# Hex_Link_Rec.net
KiCad netlist of a schematic drawn in Altium Designer
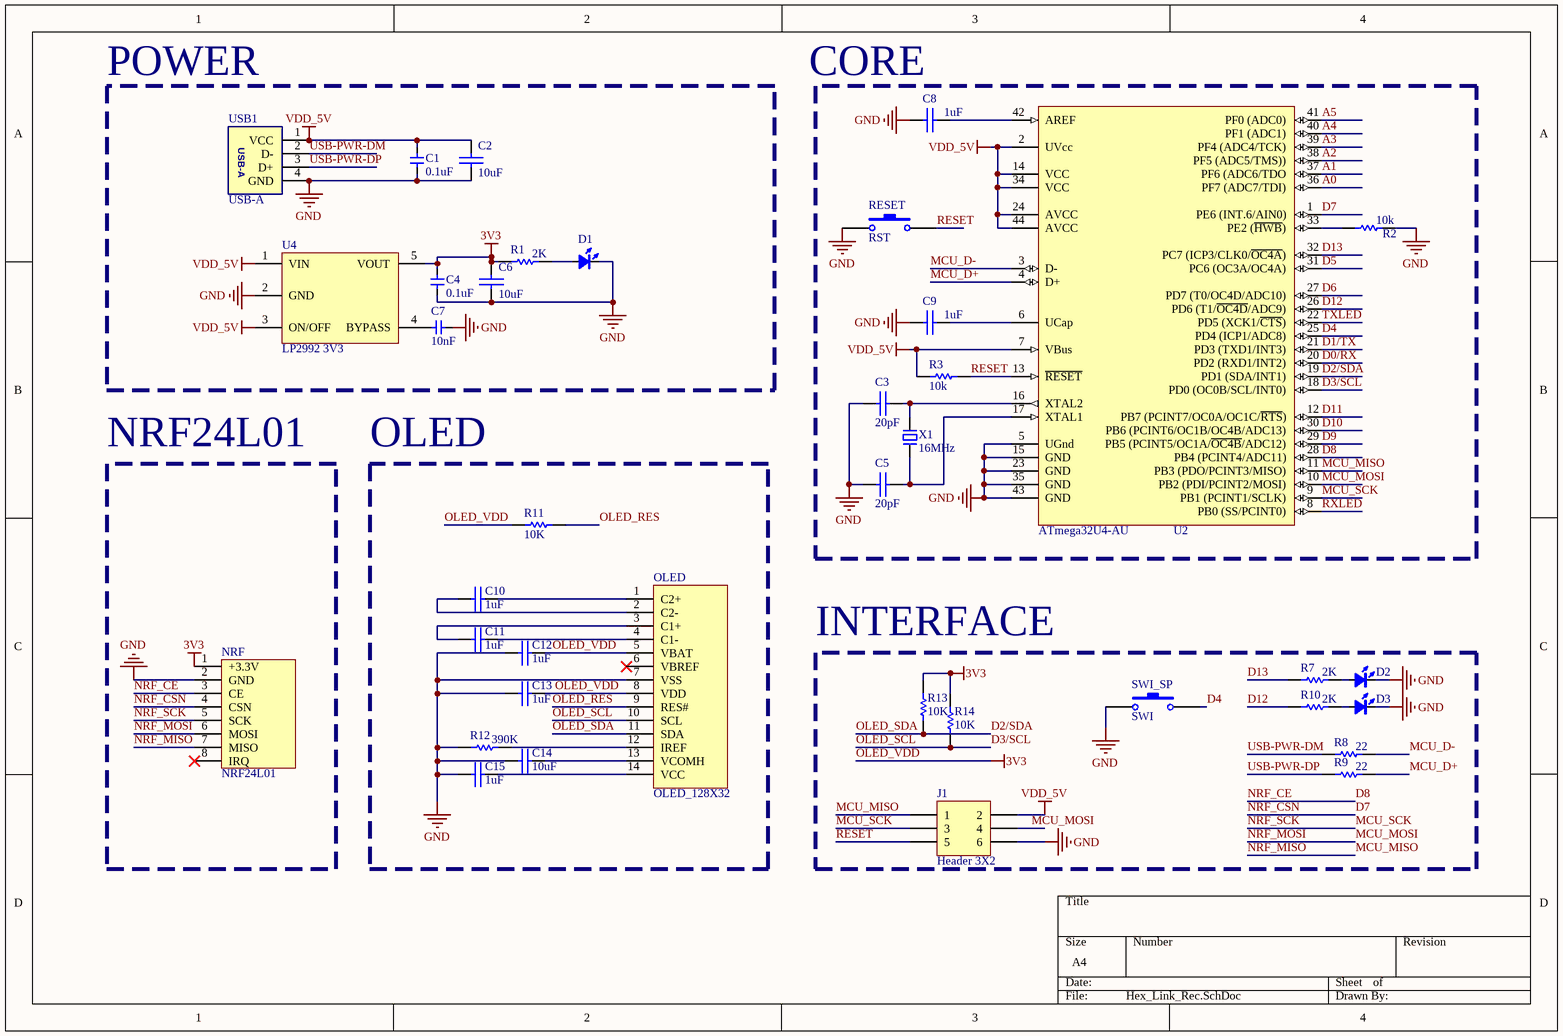
[diagram p0: Hex_Link_Rec.SchDoc]

(export (version "E")
  (design (tool "Eeschema 10.0.6"))
  (components
    (comp (ref "C1")
      (value "0.1uF")
      (footprint "CAP_0402")
      (description "Capacitor")
      (libsource (lib "MyPcbLib") (part "电容-0402"))
    )
    (comp (ref "C2")
      (value "10uF")
      (footprint "CAP_0402")
      (description "无极性电容")
      (libsource (lib "电容") (part "CAP"))
    )
    (comp (ref "C3")
      (value "20pF")
      (footprint "CAP_0402")
      (description "无极性电容")
      (libsource (lib "电容") (part "CAP"))
    )
    (comp (ref "C4")
      (value "0.1uF")
      (footprint "CAP_0402")
      (description "Capacitor")
      (libsource (lib "MyPcbLib") (part "电容-0402"))
    )
    (comp (ref "C5")
      (value "20pF")
      (footprint "CAP_0402")
      (description "无极性电容")
      (libsource (lib "电容") (part "CAP"))
    )
    (comp (ref "C6")
      (value "10uF")
      (footprint "CAP_0402")
      (description "无极性电容")
      (libsource (lib "电容") (part "CAP"))
    )
    (comp (ref "C7")
      (value "10nF")
      (footprint "CAP_0402")
      (description "Capacitor")
      (libsource (lib "MyPcbLib") (part "电容-0402"))
    )
    (comp (ref "C8")
      (value "1uF")
      (footprint "CAP_0402")
      (description "无极性电容")
      (libsource (lib "电容") (part "CAP"))
    )
    (comp (ref "C9")
      (value "1uF")
      (footprint "CAP_0402")
      (description "无极性电容")
      (libsource (lib "电容") (part "CAP"))
    )
    (comp (ref "C10")
      (value "1uF")
      (footprint "CAP_0402")
      (description "无极性电容")
      (libsource (lib "电容") (part "CAP"))
    )
    (comp (ref "C11")
      (value "1uF")
      (footprint "CAP_0402")
      (description "无极性电容")
      (libsource (lib "电容") (part "CAP"))
    )
    (comp (ref "C12")
      (value "1uF")
      (footprint "CAP_0402")
      (description "无极性电容")
      (libsource (lib "电容") (part "CAP"))
    )
    (comp (ref "C13")
      (value "1uF")
      (footprint "CAP_0402")
      (description "无极性电容")
      (libsource (lib "电容") (part "CAP"))
    )
    (comp (ref "C14")
      (value "10uF")
      (footprint "CAP_0402")
      (description "无极性电容")
      (libsource (lib "电容") (part "CAP"))
    )
    (comp (ref "C15")
      (value "1uF")
      (footprint "CAP_0402")
      (description "无极性电容")
      (libsource (lib "电容") (part "CAP"))
    )
    (comp (ref "D1")
      (value "color?")
      (footprint "LED_0402_RED")
      (description "LED")
      (libsource (lib "KitSprout") (part "LED_0402"))
    )
    (comp (ref "D2")
      (value "color?")
      (footprint "LED_0402_RED")
      (description "LED")
      (libsource (lib "KitSprout") (part "LED_0402"))
    )
    (comp (ref "D3")
      (value "color?")
      (footprint "LED_0402_RED")
      (description "LED")
      (libsource (lib "KitSprout") (part "LED_0402"))
    )
    (comp (ref "J1")
      (value "Header 3X2")
      (footprint "HDR2X3")
      (description "Header, 3-Pin, Dual row")
      (fields (field (name "PUBLISHER") "Altium Limited"))
      (libsource (lib "Miscellaneous Connectors") (part "Header 3X2"))
    )
    (comp (ref "NRF")
      (value "NRF24L01")
      (footprint "NRF24l01-SMD")
      (libsource (lib "未分类IC") (part "NRF24L01"))
    )
    (comp (ref "OLED")
      (value "OLED_128X32")
      (footprint "OLED_128X32")
      (libsource (lib "未分类IC") (part "OLED_128X32"))
    )
    (comp (ref "R1") (value "2K") (footprint "RES_0402") (libsource (lib "电阻") (part "RES")))
    (comp (ref "R2") (value "10k") (footprint "RES_0402") (libsource (lib "电阻") (part "RES")))
    (comp (ref "R3") (value "10k") (footprint "RES_0402") (libsource (lib "电阻") (part "RES")))
    (comp (ref "R7") (value "2K") (footprint "RES_0402") (libsource (lib "电阻") (part "RES")))
    (comp (ref "R8") (value "22") (footprint "RES_0402") (libsource (lib "电阻") (part "RES")))
    (comp (ref "R9") (value "22") (footprint "RES_0402") (libsource (lib "电阻") (part "RES")))
    (comp (ref "R10") (value "2K") (footprint "RES_0402") (libsource (lib "电阻") (part "RES")))
    (comp (ref "R11") (value "10K") (footprint "RES_0402") (libsource (lib "电阻") (part "RES")))
    (comp (ref "R12") (value "390K") (footprint "RES_0402") (libsource (lib "电阻") (part "RES")))
    (comp (ref "R13") (value "10K") (footprint "RES_0402") (libsource (lib "电阻") (part "RES")))
    (comp (ref "R14") (value "10K") (footprint "RES_0402") (libsource (lib "电阻") (part "RES")))
    (comp (ref "RESET")
      (value "RST")
      (footprint "SW_PB")
      (description "Switch")
      (fields (field (name "PUBLISHER") "Altium Limited"))
      (libsource (lib "未分类IC") (part "SW-PB"))
    )
    (comp (ref "SWI_SP")
      (value "SWI")
      (footprint "SW_PB")
      (description "Switch")
      (fields (field (name "PUBLISHER") "Altium Limited"))
      (libsource (lib "未分类IC") (part "SW-PB"))
    )
    (comp (ref "U2")
      (value "ATmega32U4-AU")
      (footprint "44ML_N")
      (fields (field (name "PUBLISHER") "Altium Limited"))
      (libsource (lib "Atmel Microcontroller 8-Bit megaAVR") (part "ATmega32U4-AU"))
    )
    (comp (ref "U4")
      (value "LP2992 3V3")
      (footprint "SOT23-5")
      (description "LDO")
      (libsource (lib "MyPcbLib") (part "LP2992"))
    )
    (comp (ref "USB1") (value "USB-A") (footprint "USB_A/P_B") (libsource (lib "USB") (part "USB-A")))
    (comp (ref "X1")
      (value "16MHz")
      (footprint "OSC 5032-2P")
      (description "2脚无源脚晶振")
      (libsource (lib "晶振") (part "XTAL-2P"))
    )
  )
  (nets
    (net (code "1") (name "/A0") (class "Default")
      (node (ref "U2") (pin "36") (pinfunction "PF7_(ADC7/TDI)_36") (pintype "bidirectional"))
    )
    (net (code "2") (name "/A1") (class "Default")
      (node (ref "U2") (pin "37") (pinfunction "PF6_(ADC6/TDO_37") (pintype "bidirectional"))
    )
    (net (code "3") (name "/A2") (class "Default")
      (node (ref "U2") (pin "38") (pinfunction "PF5_(ADC5/TMS))_38") (pintype "bidirectional"))
    )
    (net (code "4") (name "/A3") (class "Default")
      (node (ref "U2") (pin "39") (pinfunction "PF4_(ADC4/TCK)_39") (pintype "bidirectional"))
    )
    (net (code "5") (name "/A4") (class "Default")
      (node (ref "U2") (pin "40") (pinfunction "PF1_(ADC1)_40") (pintype "bidirectional"))
    )
    (net (code "6") (name "/A5") (class "Default")
      (node (ref "U2") (pin "41") (pinfunction "PF0_(ADC0)_41") (pintype "bidirectional"))
    )
    (net (code "7") (name "/D0{slash}RX") (class "Default")
      (node (ref "U2") (pin "20") (pinfunction "PD2_(RXD1/INT2)_20") (pintype "bidirectional"))
    )
    (net (code "8") (name "/D1{slash}TX") (class "Default")
      (node (ref "U2") (pin "21") (pinfunction "PD3_(TXD1/INT3)_21") (pintype "bidirectional"))
    )
    (net (code "9") (name "/D2{slash}SDA") (class "Default")
      (node (ref "OLED") (pin "11") (pinfunction "SDA_11") (pintype "passive"))
      (node (ref "R13") (pin "1") (pinfunction "1_1") (pintype "passive"))
      (node (ref "U2") (pin "19") (pinfunction "PD1_(SDA/INT1)_19") (pintype "bidirectional"))
    )
    (net (code "10") (name "/D3{slash}SCL") (class "Default")
      (node (ref "OLED") (pin "10") (pinfunction "SCL_10") (pintype "passive"))
      (node (ref "R14") (pin "1") (pinfunction "1_1") (pintype "passive"))
      (node (ref "U2") (pin "18") (pinfunction "PD0_(OC0B/SCL/INT0)_18") (pintype "bidirectional"))
    )
    (net (code "11") (name "/D4") (class "Default")
      (node (ref "SWI_SP") (pin "2") (pinfunction "2_2") (pintype "passive"))
      (node (ref "U2") (pin "25") (pinfunction "PD4_(ICP1/ADC8)_25") (pintype "bidirectional"))
    )
    (net (code "12") (name "/D5") (class "Default")
      (node (ref "U2") (pin "31") (pinfunction "PC6_(OC3A/OC4A)_31") (pintype "bidirectional"))
    )
    (net (code "13") (name "/D6") (class "Default")
      (node (ref "U2") (pin "27") (pinfunction "PD7_(T0/OC4D/ADC10)_27") (pintype "bidirectional"))
    )
    (net (code "14") (name "/D7") (class "Default")
      (node (ref "NRF") (pin "4") (pinfunction "CSN_4") (pintype "passive"))
      (node (ref "U2") (pin "1") (pinfunction "PE6_(INT.6/AIN0)_1") (pintype "bidirectional"))
    )
    (net (code "15") (name "/D8") (class "Default")
      (node (ref "NRF") (pin "3") (pinfunction "CE_3") (pintype "passive"))
      (node (ref "U2") (pin "28") (pinfunction "PB4_(PCINT4/ADC11)_28") (pintype "bidirectional"))
    )
    (net (code "16") (name "/D9") (class "Default")
      (node (ref "U2") (pin "29") (pinfunction "PB5_(PCINT5/OC1A/~{OC4B}/ADC12)_29") (pintype "bidirectional"))
    )
    (net (code "17") (name "/D10") (class "Default")
      (node (ref "U2") (pin "30") (pinfunction "PB6_(PCINT6/OC1B/OC4B/ADC13)_30") (pintype "bidirectional"))
    )
    (net (code "18") (name "/D11") (class "Default")
      (node (ref "U2") (pin "12") (pinfunction "PB7_(PCINT7/OC0A/OC1C/~{RTS})_12") (pintype "bidirectional"))
    )
    (net (code "19") (name "/D12") (class "Default")
      (node (ref "R10") (pin "1") (pinfunction "1_1") (pintype "passive"))
      (node (ref "U2") (pin "26") (pinfunction "PD6_(T1/~{OC4D}/ADC9)_26") (pintype "bidirectional"))
    )
    (net (code "20") (name "/D13") (class "Default")
      (node (ref "R7") (pin "1") (pinfunction "1_1") (pintype "passive"))
      (node (ref "U2") (pin "32") (pinfunction "PC7_(ICP3/CLK0/~{OC4A})_32") (pintype "bidirectional"))
    )
    (net (code "21") (name "/MCU_D+") (class "Default")
      (node (ref "R9") (pin "2") (pinfunction "2_2") (pintype "passive"))
      (node (ref "U2") (pin "4") (pinfunction "D+_4") (pintype "bidirectional"))
    )
    (net (code "22") (name "/MCU_D-") (class "Default")
      (node (ref "R8") (pin "2") (pinfunction "2_2") (pintype "passive"))
      (node (ref "U2") (pin "3") (pinfunction "D-_3") (pintype "bidirectional"))
    )
    (net (code "23") (name "/MCU_MISO") (class "Default")
      (node (ref "J1") (pin "1") (pinfunction "1_1") (pintype "passive"))
      (node (ref "NRF") (pin "7") (pinfunction "MISO_7") (pintype "passive"))
      (node (ref "U2") (pin "11") (pinfunction "PB3_(PDO/PCINT3/MISO)_11") (pintype "bidirectional"))
    )
    (net (code "24") (name "/MCU_MOSI") (class "Default")
      (node (ref "J1") (pin "4") (pinfunction "4_4") (pintype "passive"))
      (node (ref "NRF") (pin "6") (pinfunction "MOSI_6") (pintype "passive"))
      (node (ref "U2") (pin "10") (pinfunction "PB2_(PDI/PCINT2/MOSI)_10") (pintype "bidirectional"))
    )
    (net (code "25") (name "/MCU_SCK") (class "Default")
      (node (ref "J1") (pin "3") (pinfunction "3_3") (pintype "passive"))
      (node (ref "NRF") (pin "5") (pinfunction "SCK_5") (pintype "passive"))
      (node (ref "U2") (pin "9") (pinfunction "PB1_(PCINT1/SCLK)_9") (pintype "bidirectional"))
    )
    (net (code "26") (name "/OLED_RES") (class "Default")
      (node (ref "OLED") (pin "9") (pinfunction "RES#_9") (pintype "passive"))
      (node (ref "R11") (pin "2") (pinfunction "2_2") (pintype "passive"))
    )
    (net (code "27") (name "/RESET") (class "Default")
      (node (ref "J1") (pin "5") (pinfunction "5_5") (pintype "passive"))
      (node (ref "R3") (pin "1") (pinfunction "1_1") (pintype "passive"))
      (node (ref "RESET") (pin "2") (pinfunction "2_2") (pintype "passive"))
      (node (ref "U2") (pin "13") (pinfunction "~{RESET}_13") (pintype "input"))
    )
    (net (code "28") (name "/RXLED") (class "Default")
      (node (ref "U2") (pin "8") (pinfunction "PB0_(SS/PCINT0)_8") (pintype "bidirectional"))
    )
    (net (code "29") (name "/TXLED") (class "Default")
      (node (ref "U2") (pin "22") (pinfunction "PD5_(XCK1/~{CTS})_22") (pintype "bidirectional"))
    )
    (net (code "30") (name "/USB-PWR-DM") (class "Default")
      (node (ref "R8") (pin "1") (pinfunction "1_1") (pintype "passive"))
      (node (ref "USB1") (pin "2") (pinfunction "D-_2") (pintype "passive"))
    )
    (net (code "31") (name "/USB-PWR-DP") (class "Default")
      (node (ref "R9") (pin "1") (pinfunction "1_1") (pintype "passive"))
      (node (ref "USB1") (pin "3") (pinfunction "D+_3") (pintype "passive"))
    )
    (net (code "32") (name "3V3") (class "Default")
      (node (ref "C12") (pin "1") (pinfunction "1_1") (pintype "passive"))
      (node (ref "C13") (pin "1") (pinfunction "1_1") (pintype "passive"))
      (node (ref "C4") (pin "1") (pinfunction "1_1") (pintype "passive"))
      (node (ref "C6") (pin "1") (pinfunction "1_1") (pintype "passive"))
      (node (ref "NRF") (pin "1") (pinfunction "+3.3V_1") (pintype "passive"))
      (node (ref "OLED") (pin "5") (pinfunction "VBAT_5") (pintype "passive"))
      (node (ref "OLED") (pin "8") (pinfunction "VDD_8") (pintype "passive"))
      (node (ref "R1") (pin "1") (pinfunction "1_1") (pintype "passive"))
      (node (ref "R11") (pin "1") (pinfunction "1_1") (pintype "passive"))
      (node (ref "R13") (pin "2") (pinfunction "2_2") (pintype "passive"))
      (node (ref "R14") (pin "2") (pinfunction "2_2") (pintype "passive"))
      (node (ref "U4") (pin "5") (pinfunction "VOUT_5") (pintype "passive"))
    )
    (net (code "33") (name "GND") (class "Default")
      (node (ref "C1") (pin "2") (pinfunction "2_2") (pintype "passive"))
      (node (ref "C12") (pin "2") (pinfunction "2_2") (pintype "passive"))
      (node (ref "C13") (pin "2") (pinfunction "2_2") (pintype "passive"))
      (node (ref "C14") (pin "2") (pinfunction "2_2") (pintype "passive"))
      (node (ref "C15") (pin "2") (pinfunction "2_2") (pintype "passive"))
      (node (ref "C2") (pin "2") (pinfunction "2_2") (pintype "passive"))
      (node (ref "C3") (pin "2") (pinfunction "2_2") (pintype "passive"))
      (node (ref "C4") (pin "2") (pinfunction "2_2") (pintype "passive"))
      (node (ref "C5") (pin "2") (pinfunction "2_2") (pintype "passive"))
      (node (ref "C6") (pin "2") (pinfunction "2_2") (pintype "passive"))
      (node (ref "C7") (pin "1") (pinfunction "1_1") (pintype "passive"))
      (node (ref "C8") (pin "2") (pinfunction "2_2") (pintype "passive"))
      (node (ref "C9") (pin "2") (pinfunction "2_2") (pintype "passive"))
      (node (ref "D1") (pin "2") (pinfunction "K_2") (pintype "passive"))
      (node (ref "D2") (pin "2") (pinfunction "K_2") (pintype "passive"))
      (node (ref "D3") (pin "2") (pinfunction "K_2") (pintype "passive"))
      (node (ref "J1") (pin "6") (pinfunction "6_6") (pintype "passive"))
      (node (ref "NRF") (pin "2") (pinfunction "GND_2") (pintype "passive"))
      (node (ref "OLED") (pin "7") (pinfunction "VSS_7") (pintype "passive"))
      (node (ref "R12") (pin "1") (pinfunction "1_1") (pintype "passive"))
      (node (ref "R2") (pin "2") (pinfunction "2_2") (pintype "passive"))
      (node (ref "RESET") (pin "1") (pinfunction "1_1") (pintype "passive"))
      (node (ref "SWI_SP") (pin "1") (pinfunction "1_1") (pintype "passive"))
      (node (ref "U2") (pin "15") (pinfunction "GND_15") (pintype "power_in"))
      (node (ref "U2") (pin "23") (pinfunction "GND_23") (pintype "power_in"))
      (node (ref "U2") (pin "35") (pinfunction "GND_35") (pintype "power_in"))
      (node (ref "U2") (pin "43") (pinfunction "GND_43") (pintype "power_in"))
      (node (ref "U2") (pin "5") (pinfunction "UGnd_5") (pintype "power_in"))
      (node (ref "U4") (pin "2") (pinfunction "GND_2") (pintype "passive"))
      (node (ref "USB1") (pin "4") (pinfunction "GND_4") (pintype "passive"))
    )
    (net (code "34") (name "Net-(D1-A)") (class "Default")
      (node (ref "D1") (pin "1") (pinfunction "A_1") (pintype "passive"))
      (node (ref "R1") (pin "2") (pinfunction "2_2") (pintype "passive"))
    )
    (net (code "35") (name "Net-(D2-A)") (class "Default")
      (node (ref "D2") (pin "1") (pinfunction "A_1") (pintype "passive"))
      (node (ref "R7") (pin "2") (pinfunction "2_2") (pintype "passive"))
    )
    (net (code "36") (name "Net-(D3-A)") (class "Default")
      (node (ref "D3") (pin "1") (pinfunction "A_1") (pintype "passive"))
      (node (ref "R10") (pin "2") (pinfunction "2_2") (pintype "passive"))
    )
    (net (code "37") (name "Net-(OLED-C1+)") (class "Default")
      (node (ref "C11") (pin "2") (pinfunction "2_2") (pintype "passive"))
      (node (ref "OLED") (pin "3") (pinfunction "C1+_3") (pintype "passive"))
    )
    (net (code "38") (name "Net-(OLED-C1-)") (class "Default")
      (node (ref "C11") (pin "1") (pinfunction "1_1") (pintype "passive"))
      (node (ref "OLED") (pin "4") (pinfunction "C1-_4") (pintype "passive"))
    )
    (net (code "39") (name "Net-(OLED-C2+)") (class "Default")
      (node (ref "C10") (pin "1") (pinfunction "1_1") (pintype "passive"))
      (node (ref "OLED") (pin "1") (pinfunction "C2+_1") (pintype "passive"))
    )
    (net (code "40") (name "Net-(OLED-C2-)") (class "Default")
      (node (ref "C10") (pin "2") (pinfunction "2_2") (pintype "passive"))
      (node (ref "OLED") (pin "2") (pinfunction "C2-_2") (pintype "passive"))
    )
    (net (code "41") (name "Net-(OLED-IREF)") (class "Default")
      (node (ref "OLED") (pin "12") (pinfunction "IREF_12") (pintype "passive"))
      (node (ref "R12") (pin "2") (pinfunction "2_2") (pintype "passive"))
    )
    (net (code "42") (name "Net-(OLED-VCC)") (class "Default")
      (node (ref "C15") (pin "1") (pinfunction "1_1") (pintype "passive"))
      (node (ref "OLED") (pin "14") (pinfunction "VCC_14") (pintype "passive"))
    )
    (net (code "43") (name "Net-(OLED-VCOMH)") (class "Default")
      (node (ref "C14") (pin "1") (pinfunction "1_1") (pintype "passive"))
      (node (ref "OLED") (pin "13") (pinfunction "VCOMH_13") (pintype "passive"))
    )
    (net (code "44") (name "Net-(U2-AREF)") (class "Default")
      (node (ref "C8") (pin "1") (pinfunction "1_1") (pintype "passive"))
      (node (ref "U2") (pin "42") (pinfunction "AREF_42") (pintype "input"))
    )
    (net (code "45") (name "Net-(U2-PE2_(~{HWB}))") (class "Default")
      (node (ref "R2") (pin "1") (pinfunction "1_1") (pintype "passive"))
      (node (ref "U2") (pin "33") (pinfunction "PE2_(~{HWB})_33") (pintype "bidirectional"))
    )
    (net (code "46") (name "Net-(U2-UCap)") (class "Default")
      (node (ref "C9") (pin "1") (pinfunction "1_1") (pintype "passive"))
      (node (ref "U2") (pin "6") (pinfunction "UCap_6") (pintype "passive"))
    )
    (net (code "47") (name "Net-(U2-XTAL1)") (class "Default")
      (node (ref "C5") (pin "1") (pinfunction "1_1") (pintype "passive"))
      (node (ref "U2") (pin "17") (pinfunction "XTAL1_17") (pintype "input"))
      (node (ref "X1") (pin "1") (pinfunction "1_1") (pintype "passive"))
    )
    (net (code "48") (name "Net-(U2-XTAL2)") (class "Default")
      (node (ref "C3") (pin "1") (pinfunction "1_1") (pintype "passive"))
      (node (ref "U2") (pin "16") (pinfunction "XTAL2_16") (pintype "output"))
      (node (ref "X1") (pin "2") (pinfunction "2_2") (pintype "passive"))
    )
    (net (code "49") (name "Net-(U4-BYPASS)") (class "Default")
      (node (ref "C7") (pin "2") (pinfunction "2_2") (pintype "passive"))
      (node (ref "U4") (pin "4") (pinfunction "BYPASS_4") (pintype "passive"))
    )
    (net (code "50") (name "VDD_5V") (class "Default")
      (node (ref "C1") (pin "1") (pinfunction "1_1") (pintype "passive"))
      (node (ref "C2") (pin "1") (pinfunction "1_1") (pintype "passive"))
      (node (ref "J1") (pin "2") (pinfunction "2_2") (pintype "passive"))
      (node (ref "R3") (pin "2") (pinfunction "2_2") (pintype "passive"))
      (node (ref "U2") (pin "14") (pinfunction "VCC_14") (pintype "power_in"))
      (node (ref "U2") (pin "2") (pinfunction "UVcc_2") (pintype "power_in"))
      (node (ref "U2") (pin "24") (pinfunction "AVCC_24") (pintype "power_in"))
      (node (ref "U2") (pin "34") (pinfunction "VCC_34") (pintype "power_in"))
      (node (ref "U2") (pin "44") (pinfunction "AVCC_44") (pintype "power_in"))
      (node (ref "U2") (pin "7") (pinfunction "VBus_7") (pintype "input"))
      (node (ref "U4") (pin "1") (pinfunction "VIN_1") (pintype "passive"))
      (node (ref "U4") (pin "3") (pinfunction "ON/OFF_3") (pintype "passive"))
      (node (ref "USB1") (pin "1") (pinfunction "VCC_1") (pintype "passive"))
    )
    (net (code "51") (name "unconnected-(NRF-IRQ-Pad8)") (class "Default")
      (node (ref "NRF") (pin "8") (pinfunction "IRQ_8") (pintype "passive+no_connect"))
    )
    (net (code "52") (name "unconnected-(OLED-VBREF-Pad6)") (class "Default")
      (node (ref "OLED") (pin "6") (pinfunction "VBREF_6") (pintype "passive+no_connect"))
    )
  )
)
